# fpc_cable_all.net
KiCad netlist of a schematic drawn in EAGLE
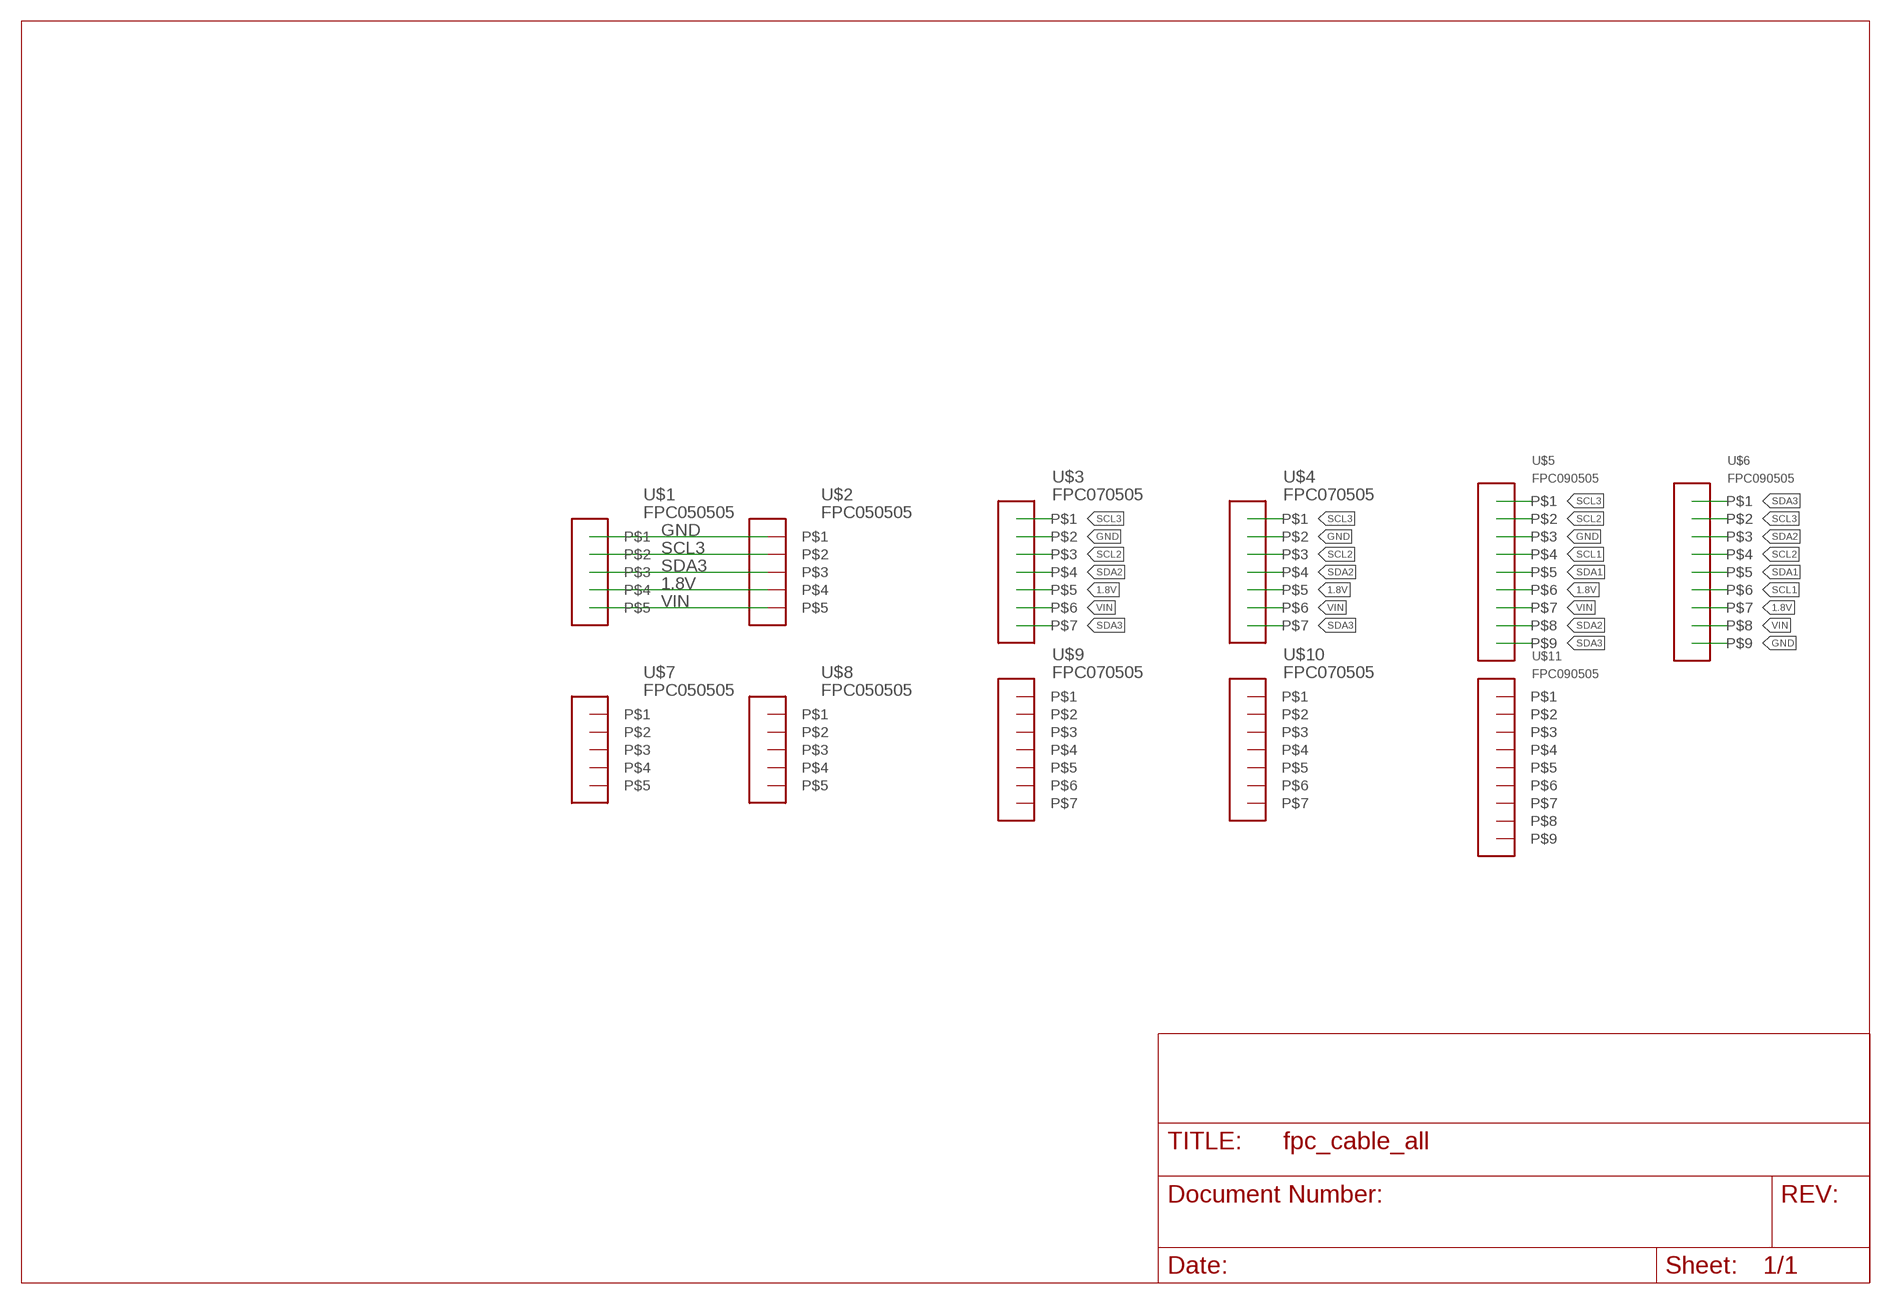
[diagram p0: schematic, sheet 1]

(export (version "E")
  (design (tool "Eeschema 10.0.6"))
  (components
    (comp (ref "U$1")
      (value "FPC050505")
      (footprint "eagle-import:FPC0505")
      (libsource (lib "eagle-import") (part "FPC050505"))
    )
    (comp (ref "U$2")
      (value "FPC050505")
      (footprint "eagle-import:FPC0505")
      (libsource (lib "eagle-import") (part "FPC050505"))
    )
    (comp (ref "U$3")
      (value "FPC070505")
      (footprint "eagle-import:FPC0705")
      (libsource (lib "eagle-import") (part "FPC070505"))
    )
    (comp (ref "U$4")
      (value "FPC070505")
      (footprint "eagle-import:FPC0705")
      (libsource (lib "eagle-import") (part "FPC070505"))
    )
    (comp (ref "U$5")
      (value "FPC090505")
      (footprint "eagle-import:FPC0905")
      (libsource (lib "eagle-import") (part "FPC090505"))
    )
    (comp (ref "U$6")
      (value "FPC090505")
      (footprint "eagle-import:FPC0905")
      (libsource (lib "eagle-import") (part "FPC090505"))
    )
    (comp (ref "U$7")
      (value "FPC050505")
      (footprint "eagle-import:FPC0505")
      (libsource (lib "eagle-import") (part "FPC050505"))
    )
    (comp (ref "U$8")
      (value "FPC050505")
      (footprint "eagle-import:FPC0505")
      (libsource (lib "eagle-import") (part "FPC050505"))
    )
    (comp (ref "U$9")
      (value "FPC070505")
      (footprint "eagle-import:FPC0705")
      (libsource (lib "eagle-import") (part "FPC070505"))
    )
    (comp (ref "U$10")
      (value "FPC070505")
      (footprint "eagle-import:FPC0705")
      (libsource (lib "eagle-import") (part "FPC070505"))
    )
    (comp (ref "U$11")
      (value "FPC090505")
      (footprint "eagle-import:FPC0905")
      (libsource (lib "eagle-import") (part "FPC090505"))
    )
  )
  (nets
    (net (code "1") (name "1.8V") (class "Default")
      (node (ref "U$1") (pin "P$4") (pinfunction "P$4_P$4") (pintype "bidirectional"))
      (node (ref "U$2") (pin "P$4") (pinfunction "P$4_P$4") (pintype "bidirectional"))
      (node (ref "U$3") (pin "P$5") (pinfunction "P$5_P$5") (pintype "bidirectional"))
      (node (ref "U$4") (pin "P$5") (pinfunction "P$5_P$5") (pintype "bidirectional"))
      (node (ref "U$5") (pin "P$6") (pinfunction "P$6_P$6") (pintype "bidirectional"))
      (node (ref "U$6") (pin "P$7") (pinfunction "P$7_P$7") (pintype "bidirectional"))
    )
    (net (code "2") (name "GND") (class "Default")
      (node (ref "U$1") (pin "P$1") (pinfunction "P$1_P$1") (pintype "bidirectional"))
      (node (ref "U$2") (pin "P$1") (pinfunction "P$1_P$1") (pintype "bidirectional"))
      (node (ref "U$3") (pin "P$2") (pinfunction "P$2_P$2") (pintype "bidirectional"))
      (node (ref "U$4") (pin "P$2") (pinfunction "P$2_P$2") (pintype "bidirectional"))
      (node (ref "U$5") (pin "P$3") (pinfunction "P$3_P$3") (pintype "bidirectional"))
      (node (ref "U$6") (pin "P$9") (pinfunction "P$9_P$9") (pintype "bidirectional"))
    )
    (net (code "3") (name "SCL1") (class "Default")
      (node (ref "U$5") (pin "P$4") (pinfunction "P$4_P$4") (pintype "bidirectional"))
      (node (ref "U$6") (pin "P$6") (pinfunction "P$6_P$6") (pintype "bidirectional"))
    )
    (net (code "4") (name "SCL2") (class "Default")
      (node (ref "U$3") (pin "P$3") (pinfunction "P$3_P$3") (pintype "bidirectional"))
      (node (ref "U$4") (pin "P$3") (pinfunction "P$3_P$3") (pintype "bidirectional"))
      (node (ref "U$5") (pin "P$2") (pinfunction "P$2_P$2") (pintype "bidirectional"))
      (node (ref "U$6") (pin "P$4") (pinfunction "P$4_P$4") (pintype "bidirectional"))
    )
    (net (code "5") (name "SCL3") (class "Default")
      (node (ref "U$1") (pin "P$2") (pinfunction "P$2_P$2") (pintype "bidirectional"))
      (node (ref "U$2") (pin "P$2") (pinfunction "P$2_P$2") (pintype "bidirectional"))
      (node (ref "U$3") (pin "P$1") (pinfunction "P$1_P$1") (pintype "bidirectional"))
      (node (ref "U$4") (pin "P$1") (pinfunction "P$1_P$1") (pintype "bidirectional"))
      (node (ref "U$5") (pin "P$1") (pinfunction "P$1_P$1") (pintype "bidirectional"))
      (node (ref "U$6") (pin "P$2") (pinfunction "P$2_P$2") (pintype "bidirectional"))
    )
    (net (code "6") (name "SDA1") (class "Default")
      (node (ref "U$5") (pin "P$5") (pinfunction "P$5_P$5") (pintype "bidirectional"))
      (node (ref "U$6") (pin "P$5") (pinfunction "P$5_P$5") (pintype "bidirectional"))
    )
    (net (code "7") (name "SDA2") (class "Default")
      (node (ref "U$3") (pin "P$4") (pinfunction "P$4_P$4") (pintype "bidirectional"))
      (node (ref "U$4") (pin "P$4") (pinfunction "P$4_P$4") (pintype "bidirectional"))
      (node (ref "U$5") (pin "P$8") (pinfunction "P$8_P$8") (pintype "bidirectional"))
      (node (ref "U$6") (pin "P$3") (pinfunction "P$3_P$3") (pintype "bidirectional"))
    )
    (net (code "8") (name "SDA3") (class "Default")
      (node (ref "U$1") (pin "P$3") (pinfunction "P$3_P$3") (pintype "bidirectional"))
      (node (ref "U$2") (pin "P$3") (pinfunction "P$3_P$3") (pintype "bidirectional"))
      (node (ref "U$3") (pin "P$7") (pinfunction "P$7_P$7") (pintype "bidirectional"))
      (node (ref "U$4") (pin "P$7") (pinfunction "P$7_P$7") (pintype "bidirectional"))
      (node (ref "U$5") (pin "P$9") (pinfunction "P$9_P$9") (pintype "bidirectional"))
      (node (ref "U$6") (pin "P$1") (pinfunction "P$1_P$1") (pintype "bidirectional"))
    )
    (net (code "9") (name "VIN") (class "Default")
      (node (ref "U$1") (pin "P$5") (pinfunction "P$5_P$5") (pintype "bidirectional"))
      (node (ref "U$2") (pin "P$5") (pinfunction "P$5_P$5") (pintype "bidirectional"))
      (node (ref "U$3") (pin "P$6") (pinfunction "P$6_P$6") (pintype "bidirectional"))
      (node (ref "U$4") (pin "P$6") (pinfunction "P$6_P$6") (pintype "bidirectional"))
      (node (ref "U$5") (pin "P$7") (pinfunction "P$7_P$7") (pintype "bidirectional"))
      (node (ref "U$6") (pin "P$8") (pinfunction "P$8_P$8") (pintype "bidirectional"))
    )
    (net (code "10") (name "unconnected-(U$7-PadP$1)") (class "Default")
      (node (ref "U$7") (pin "P$1") (pinfunction "P$1_P$1") (pintype "bidirectional"))
    )
    (net (code "11") (name "unconnected-(U$7-PadP$2)") (class "Default")
      (node (ref "U$7") (pin "P$2") (pinfunction "P$2_P$2") (pintype "bidirectional"))
    )
    (net (code "12") (name "unconnected-(U$7-PadP$3)") (class "Default")
      (node (ref "U$7") (pin "P$3") (pinfunction "P$3_P$3") (pintype "bidirectional"))
    )
    (net (code "13") (name "unconnected-(U$7-PadP$4)") (class "Default")
      (node (ref "U$7") (pin "P$4") (pinfunction "P$4_P$4") (pintype "bidirectional"))
    )
    (net (code "14") (name "unconnected-(U$7-PadP$5)") (class "Default")
      (node (ref "U$7") (pin "P$5") (pinfunction "P$5_P$5") (pintype "bidirectional"))
    )
    (net (code "15") (name "unconnected-(U$8-PadP$1)") (class "Default")
      (node (ref "U$8") (pin "P$1") (pinfunction "P$1_P$1") (pintype "bidirectional"))
    )
    (net (code "16") (name "unconnected-(U$8-PadP$2)") (class "Default")
      (node (ref "U$8") (pin "P$2") (pinfunction "P$2_P$2") (pintype "bidirectional"))
    )
    (net (code "17") (name "unconnected-(U$8-PadP$3)") (class "Default")
      (node (ref "U$8") (pin "P$3") (pinfunction "P$3_P$3") (pintype "bidirectional"))
    )
    (net (code "18") (name "unconnected-(U$8-PadP$4)") (class "Default")
      (node (ref "U$8") (pin "P$4") (pinfunction "P$4_P$4") (pintype "bidirectional"))
    )
    (net (code "19") (name "unconnected-(U$8-PadP$5)") (class "Default")
      (node (ref "U$8") (pin "P$5") (pinfunction "P$5_P$5") (pintype "bidirectional"))
    )
    (net (code "20") (name "unconnected-(U$9-PadP$1)") (class "Default")
      (node (ref "U$9") (pin "P$1") (pinfunction "P$1_P$1") (pintype "bidirectional"))
    )
    (net (code "21") (name "unconnected-(U$9-PadP$2)") (class "Default")
      (node (ref "U$9") (pin "P$2") (pinfunction "P$2_P$2") (pintype "bidirectional"))
    )
    (net (code "22") (name "unconnected-(U$9-PadP$3)") (class "Default")
      (node (ref "U$9") (pin "P$3") (pinfunction "P$3_P$3") (pintype "bidirectional"))
    )
    (net (code "23") (name "unconnected-(U$9-PadP$4)") (class "Default")
      (node (ref "U$9") (pin "P$4") (pinfunction "P$4_P$4") (pintype "bidirectional"))
    )
    (net (code "24") (name "unconnected-(U$9-PadP$5)") (class "Default")
      (node (ref "U$9") (pin "P$5") (pinfunction "P$5_P$5") (pintype "bidirectional"))
    )
    (net (code "25") (name "unconnected-(U$9-PadP$6)") (class "Default")
      (node (ref "U$9") (pin "P$6") (pinfunction "P$6_P$6") (pintype "bidirectional"))
    )
    (net (code "26") (name "unconnected-(U$9-PadP$7)") (class "Default")
      (node (ref "U$9") (pin "P$7") (pinfunction "P$7_P$7") (pintype "bidirectional"))
    )
    (net (code "27") (name "unconnected-(U$10-PadP$1)") (class "Default")
      (node (ref "U$10") (pin "P$1") (pinfunction "P$1_P$1") (pintype "bidirectional"))
    )
    (net (code "28") (name "unconnected-(U$10-PadP$2)") (class "Default")
      (node (ref "U$10") (pin "P$2") (pinfunction "P$2_P$2") (pintype "bidirectional"))
    )
    (net (code "29") (name "unconnected-(U$10-PadP$3)") (class "Default")
      (node (ref "U$10") (pin "P$3") (pinfunction "P$3_P$3") (pintype "bidirectional"))
    )
    (net (code "30") (name "unconnected-(U$10-PadP$4)") (class "Default")
      (node (ref "U$10") (pin "P$4") (pinfunction "P$4_P$4") (pintype "bidirectional"))
    )
    (net (code "31") (name "unconnected-(U$10-PadP$5)") (class "Default")
      (node (ref "U$10") (pin "P$5") (pinfunction "P$5_P$5") (pintype "bidirectional"))
    )
    (net (code "32") (name "unconnected-(U$10-PadP$6)") (class "Default")
      (node (ref "U$10") (pin "P$6") (pinfunction "P$6_P$6") (pintype "bidirectional"))
    )
    (net (code "33") (name "unconnected-(U$10-PadP$7)") (class "Default")
      (node (ref "U$10") (pin "P$7") (pinfunction "P$7_P$7") (pintype "bidirectional"))
    )
    (net (code "34") (name "unconnected-(U$11-PadP$1)") (class "Default")
      (node (ref "U$11") (pin "P$1") (pinfunction "P$1_P$1") (pintype "bidirectional"))
    )
    (net (code "35") (name "unconnected-(U$11-PadP$2)") (class "Default")
      (node (ref "U$11") (pin "P$2") (pinfunction "P$2_P$2") (pintype "bidirectional"))
    )
    (net (code "36") (name "unconnected-(U$11-PadP$3)") (class "Default")
      (node (ref "U$11") (pin "P$3") (pinfunction "P$3_P$3") (pintype "bidirectional"))
    )
    (net (code "37") (name "unconnected-(U$11-PadP$4)") (class "Default")
      (node (ref "U$11") (pin "P$4") (pinfunction "P$4_P$4") (pintype "bidirectional"))
    )
    (net (code "38") (name "unconnected-(U$11-PadP$5)") (class "Default")
      (node (ref "U$11") (pin "P$5") (pinfunction "P$5_P$5") (pintype "bidirectional"))
    )
    (net (code "39") (name "unconnected-(U$11-PadP$6)") (class "Default")
      (node (ref "U$11") (pin "P$6") (pinfunction "P$6_P$6") (pintype "bidirectional"))
    )
    (net (code "40") (name "unconnected-(U$11-PadP$7)") (class "Default")
      (node (ref "U$11") (pin "P$7") (pinfunction "P$7_P$7") (pintype "bidirectional"))
    )
    (net (code "41") (name "unconnected-(U$11-PadP$8)") (class "Default")
      (node (ref "U$11") (pin "P$8") (pinfunction "P$8_P$8") (pintype "bidirectional"))
    )
    (net (code "42") (name "unconnected-(U$11-PadP$9)") (class "Default")
      (node (ref "U$11") (pin "P$9") (pinfunction "P$9_P$9") (pintype "bidirectional"))
    )
  )
)
